# USB-C.net
KiCad netlist of a schematic drawn in Altium Designer
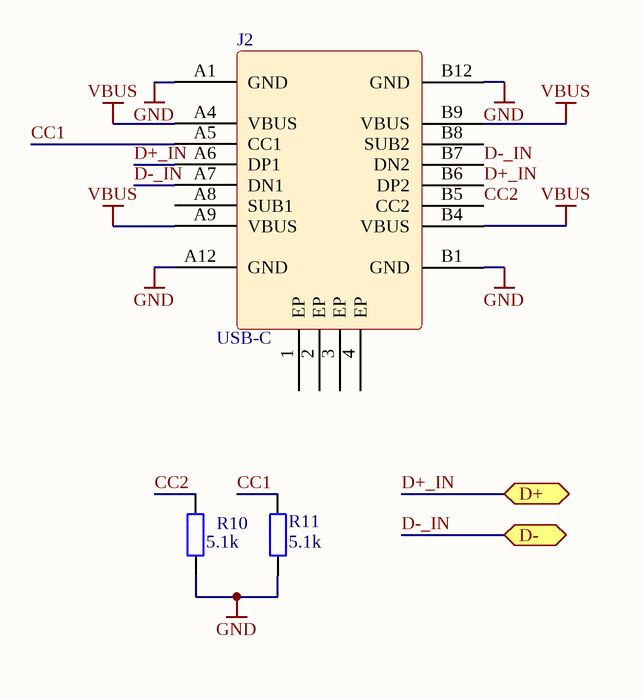
[diagram p0: USB-C.SchDoc]

(export (version "E")
  (design (tool "Eeschema 10.0.6"))
  (components
    (comp (ref "J2")
      (value "USB-C")
      (footprint "USB-C_1")
      (libsource (lib "passive_components") (part "USB-C_1"))
    )
    (comp (ref "R10") (value "5.1k") (footprint "0402_RES") (libsource (lib "passive_components") (part "R")))
    (comp (ref "R11") (value "5.1k") (footprint "0402_RES") (libsource (lib "passive_components") (part "R")))
  )
  (nets
    (net (code "1") (name "/CC1") (class "Default")
      (node (ref "J2") (pin "A5") (pinfunction "CC1_A5") (pintype "passive"))
      (node (ref "R11") (pin "2") (pinfunction "26_2") (pintype "passive"))
    )
    (net (code "2") (name "/CC2") (class "Default")
      (node (ref "J2") (pin "B5") (pinfunction "CC2_B5") (pintype "passive"))
      (node (ref "R10") (pin "2") (pinfunction "26_2") (pintype "passive"))
    )
    (net (code "3") (name "/D+_IN") (class "Default")
      (node (ref "J2") (pin "A6") (pinfunction "DP1_A6") (pintype "passive"))
      (node (ref "J2") (pin "B6") (pinfunction "DP2_B6") (pintype "passive"))
    )
    (net (code "4") (name "/D-_IN") (class "Default")
      (node (ref "J2") (pin "A7") (pinfunction "DN1_A7") (pintype "passive"))
      (node (ref "J2") (pin "B7") (pinfunction "DN2_B7") (pintype "passive"))
    )
    (net (code "5") (name "GND") (class "Default")
      (node (ref "J2") (pin "A1") (pinfunction "GND_A1") (pintype "passive"))
      (node (ref "J2") (pin "A12") (pinfunction "GND_A12") (pintype "passive"))
      (node (ref "J2") (pin "B1") (pinfunction "GND_B1") (pintype "passive"))
      (node (ref "J2") (pin "B12") (pinfunction "GND_B12") (pintype "passive"))
      (node (ref "R10") (pin "1") (pinfunction "25_1") (pintype "passive"))
      (node (ref "R11") (pin "1") (pinfunction "25_1") (pintype "passive"))
    )
    (net (code "6") (name "VBUS") (class "Default")
      (node (ref "J2") (pin "A4") (pinfunction "VBUS_A4") (pintype "passive"))
      (node (ref "J2") (pin "A9") (pinfunction "VBUS_A9") (pintype "passive"))
      (node (ref "J2") (pin "B4") (pinfunction "VBUS_B4") (pintype "passive"))
      (node (ref "J2") (pin "B9") (pinfunction "VBUS_B9") (pintype "passive"))
    )
    (net (code "7") (name "unconnected-(J2-EP-Pad1)") (class "Default")
      (node (ref "J2") (pin "1") (pinfunction "EP_1") (pintype "passive"))
    )
    (net (code "8") (name "unconnected-(J2-EP-Pad2)") (class "Default")
      (node (ref "J2") (pin "2") (pinfunction "EP_2") (pintype "passive"))
    )
    (net (code "9") (name "unconnected-(J2-EP-Pad3)") (class "Default")
      (node (ref "J2") (pin "3") (pinfunction "EP_3") (pintype "passive"))
    )
    (net (code "10") (name "unconnected-(J2-EP-Pad4)") (class "Default")
      (node (ref "J2") (pin "4") (pinfunction "EP_4") (pintype "passive"))
    )
    (net (code "11") (name "unconnected-(J2-SUB1-PadA8)") (class "Default")
      (node (ref "J2") (pin "A8") (pinfunction "SUB1_A8") (pintype "passive"))
    )
    (net (code "12") (name "unconnected-(J2-SUB2-PadB8)") (class "Default")
      (node (ref "J2") (pin "B8") (pinfunction "SUB2_B8") (pintype "passive"))
    )
  )
)
